# Mozard_Nano.net
KiCad netlist of a schematic drawn in EAGLE
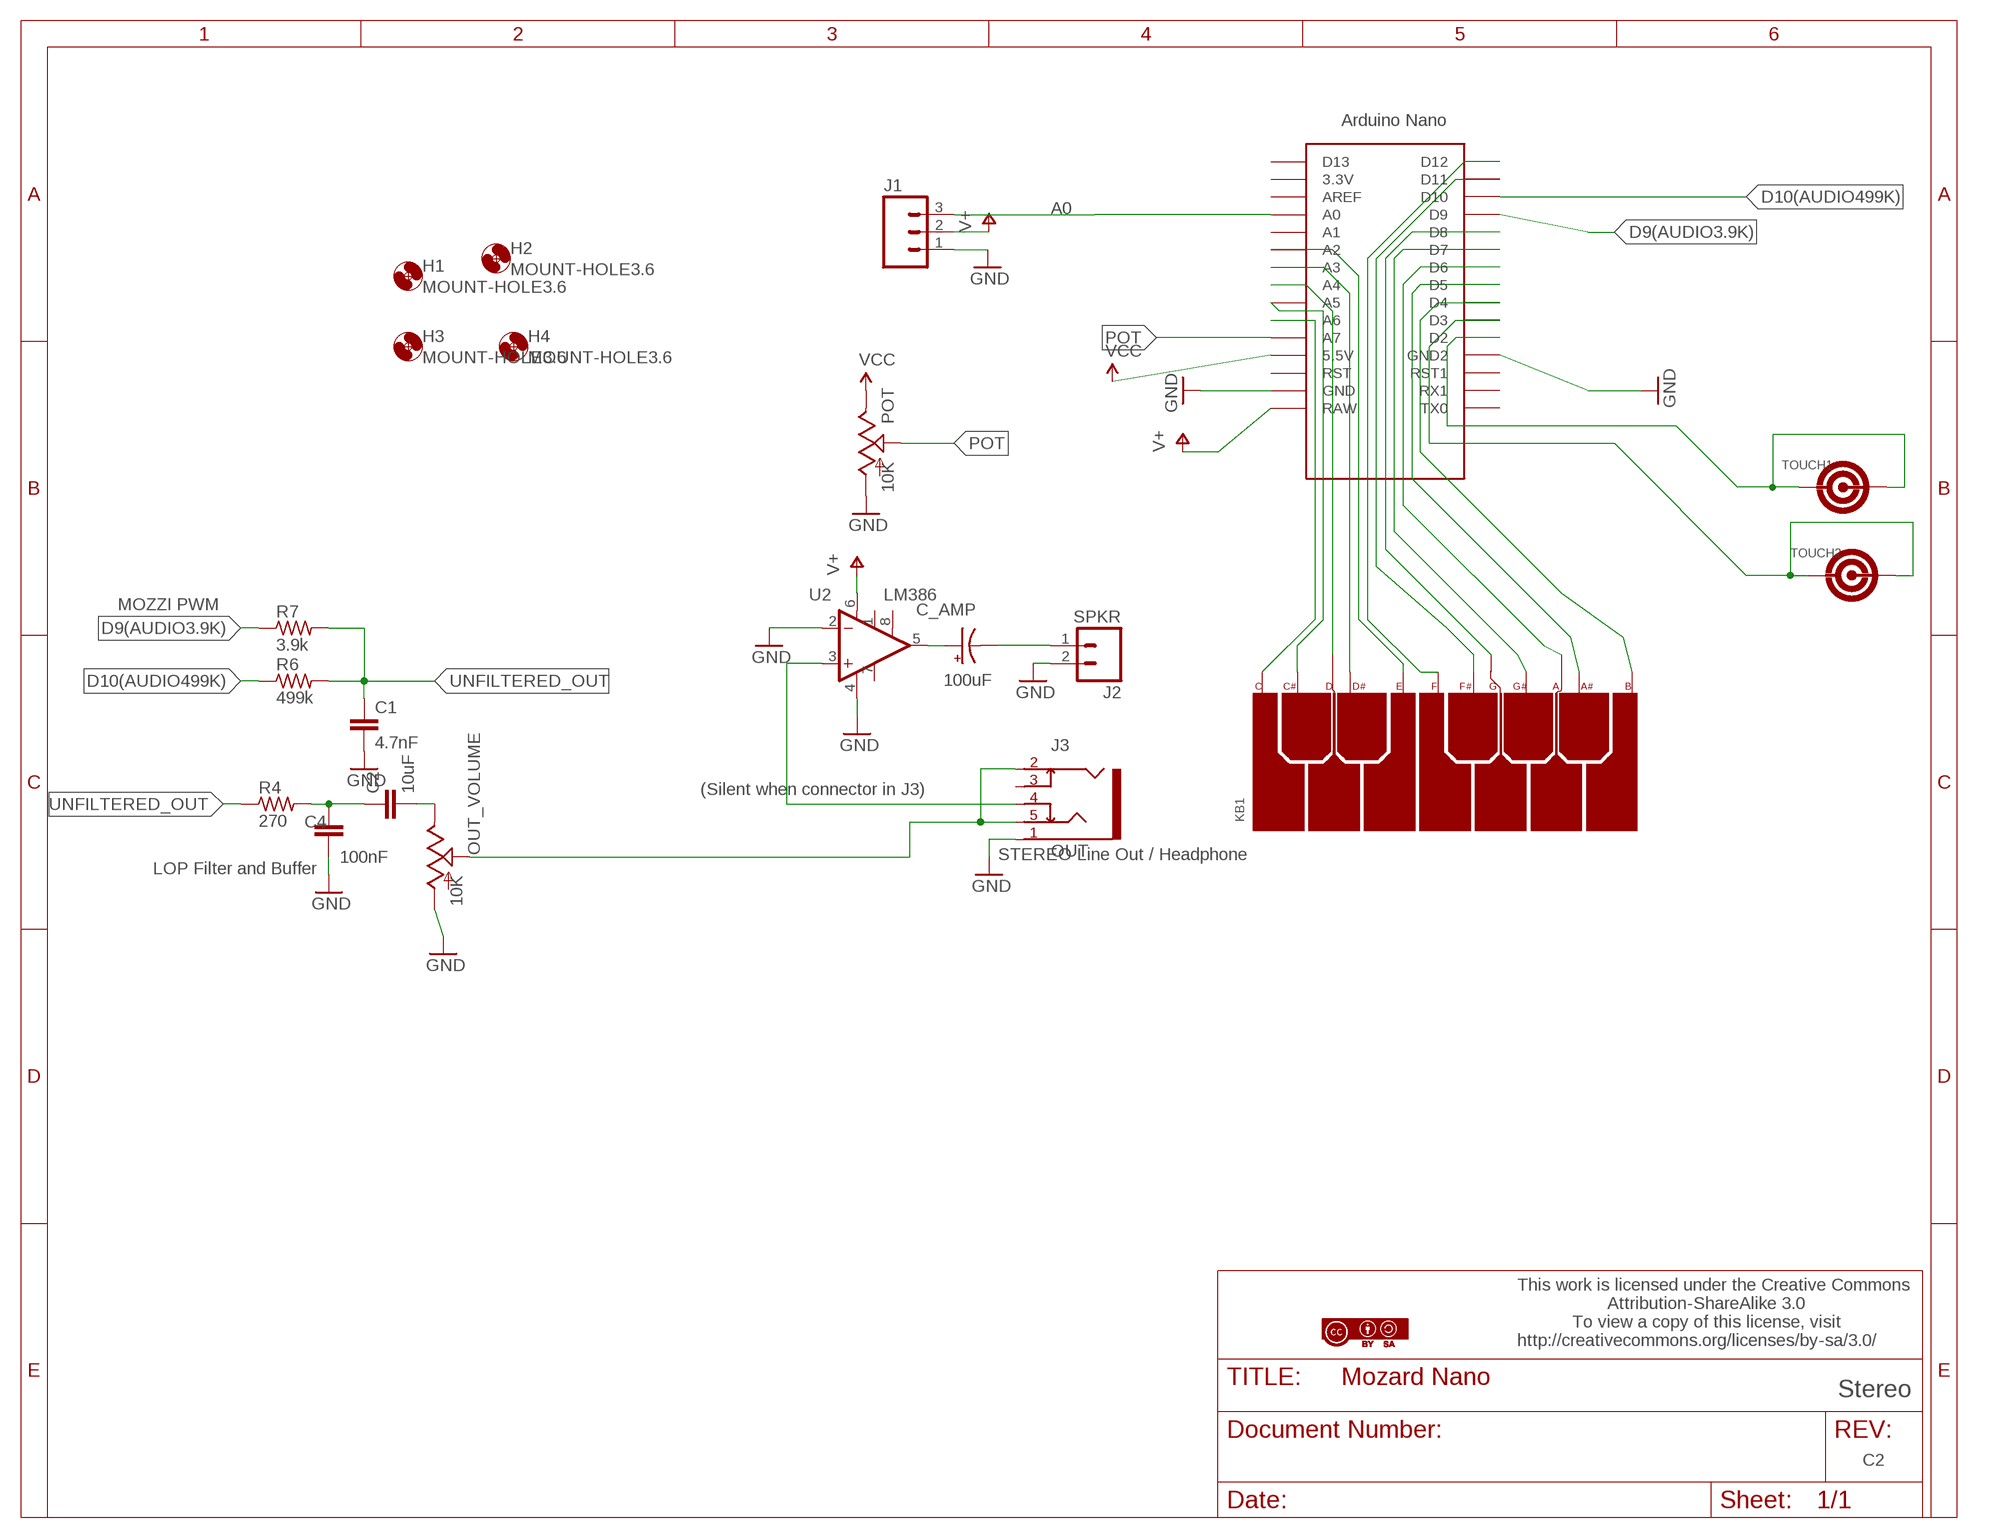
[diagram p0: schematic, sheet 1]

(export (version "E")
  (design (tool "Eeschema 10.0.6"))
  (components
    (comp (ref "C1")
      (value "4.7nF")
      (footprint "eagle-import:CAP-PTH-SMALL-KIT")
      (libsource (lib "eagle-import") (part "0.1UF-50V-20%(PTH)KIT-EZ"))
    )
    (comp (ref "C2")
      (value "10uF")
      (footprint "eagle-import:CAP-PTH-SMALL-KIT")
      (libsource (lib "eagle-import") (part "0.1UF-50V-20%(PTH)KIT-EZ"))
    )
    (comp (ref "C4")
      (value "100nF")
      (footprint "eagle-import:CAP-PTH-SMALL-KIT")
      (libsource (lib "eagle-import") (part "0.1UF-50V-20%(PTH)KIT-EZ"))
    )
    (comp (ref "C_AMP")
      (value "100uF")
      (footprint "eagle-import:CPOL-RADIAL-10UF-25V")
      (libsource (lib "eagle-import") (part "CPOL-RADIAL-10UF-25V"))
    )
    (comp (ref "H1")
      (value "MOUNT-HOLE3.6")
      (footprint "eagle-import:3,6")
      (libsource (lib "eagle-import") (part "MOUNT-HOLE3.6"))
    )
    (comp (ref "H2")
      (value "MOUNT-HOLE3.6")
      (footprint "eagle-import:3,6")
      (libsource (lib "eagle-import") (part "MOUNT-HOLE3.6"))
    )
    (comp (ref "H3")
      (value "MOUNT-HOLE3.6")
      (footprint "eagle-import:3,6")
      (libsource (lib "eagle-import") (part "MOUNT-HOLE3.6"))
    )
    (comp (ref "H4")
      (value "MOUNT-HOLE3.6")
      (footprint "eagle-import:3,6")
      (libsource (lib "eagle-import") (part "MOUNT-HOLE3.6"))
    )
    (comp (ref "J1")
      (value "M03SCREW")
      (footprint "eagle-import:SCREWTERMINAL-3.5MM-3")
      (libsource (lib "eagle-import") (part "M03SCREW"))
    )
    (comp (ref "J2")
      (value "SPKR")
      (footprint "eagle-import:SCREWTERMINAL-3.5MM-2")
      (libsource (lib "eagle-import") (part "M023.5MM"))
    )
    (comp (ref "J3")
      (value "OUT")
      (footprint "eagle-import:STEREO-AUDIO-3.5MM-SWITCHED")
      (libsource (lib "eagle-import") (part "STEREO-AUDIO-3.5MM-SWITCHED"))
    )
    (comp (ref "KB1")
      (value "PCB-KEYBOARD4")
      (footprint "eagle-import:PCB-KEYBOARD4")
      (libsource (lib "eagle-import") (part "PCB-KEYBOARD4"))
    )
    (comp (ref "OUT_VOLUME")
      (value "10K")
      (footprint "eagle-import:ALPS_POT_KIT")
      (libsource (lib "eagle-import") (part "POTALPS-KIT"))
    )
    (comp (ref "POT")
      (value "10K")
      (footprint "eagle-import:ALPS_POT_KIT")
      (libsource (lib "eagle-import") (part "POTALPS-KIT"))
    )
    (comp (ref "R4")
      (value "270")
      (footprint "eagle-import:0204_5")
      (libsource (lib "eagle-import") (part "R-US_0204/5"))
    )
    (comp (ref "R6")
      (value "499k")
      (footprint "eagle-import:0204_5")
      (libsource (lib "eagle-import") (part "R-US_0204/5"))
    )
    (comp (ref "R7")
      (value "3.9k")
      (footprint "eagle-import:0204_5")
      (libsource (lib "eagle-import") (part "R-US_0204/5"))
    )
    (comp (ref "TOUCH1")
      (value "PCB-TOUCHPAD2")
      (footprint "eagle-import:PCB-TOUCHPAD2")
      (libsource (lib "eagle-import") (part "PCB-TOUCHPAD2"))
    )
    (comp (ref "TOUCH2")
      (value "PCB-TOUCHPAD2")
      (footprint "eagle-import:PCB-TOUCHPAD2")
      (libsource (lib "eagle-import") (part "PCB-TOUCHPAD2"))
    )
    (comp (ref "U$1")
      (value "NANO")
      (footprint "eagle-import:NANO")
      (libsource (lib "eagle-import") (part "NANO"))
    )
    (comp (ref "U$2")
      (value "CC-BY-SA-LOGO2")
      (footprint "eagle-import:CC-BY-SA-LOGO2")
      (libsource (lib "eagle-import") (part "CC-BY-SA-LOGO2"))
    )
    (comp (ref "U2")
      (value "LM386")
      (footprint "eagle-import:DIP08")
      (libsource (lib "eagle-import") (part "LM386"))
    )
  )
  (nets
    (net (code "1") (name "/A0") (class "Default")
      (node (ref "J1") (pin "3") (pinfunction "3_3") (pintype "passive"))
      (node (ref "U$1") (pin "A0") (pinfunction "A0_A0") (pintype "bidirectional"))
    )
    (net (code "2") (name "D9(AUDIO3.9K)") (class "Default")
      (node (ref "R7") (pin "1") (pinfunction "1_1") (pintype "passive"))
      (node (ref "U$1") (pin "D9") (pinfunction "D9_D9") (pintype "bidirectional"))
    )
    (net (code "3") (name "D10(AUDIO499K)") (class "Default")
      (node (ref "R6") (pin "1") (pinfunction "1_1") (pintype "passive"))
      (node (ref "U$1") (pin "D10") (pinfunction "D10_D10") (pintype "bidirectional"))
    )
    (net (code "4") (name "GND") (class "Default")
      (node (ref "C1") (pin "2") (pinfunction "2_2") (pintype "passive"))
      (node (ref "C4") (pin "2") (pinfunction "2_2") (pintype "passive"))
      (node (ref "J1") (pin "1") (pinfunction "1_1") (pintype "passive"))
      (node (ref "J2") (pin "2") (pinfunction "2_2") (pintype "passive"))
      (node (ref "J3") (pin "1") (pinfunction "1_1") (pintype "bidirectional"))
      (node (ref "OUT_VOLUME") (pin "P$3") (pinfunction "A_P$3") (pintype "passive"))
      (node (ref "POT") (pin "P$3") (pinfunction "A_P$3") (pintype "passive"))
      (node (ref "U$1") (pin "GND") (pinfunction "GND_GND") (pintype "bidirectional"))
      (node (ref "U$1") (pin "GND1") (pinfunction "GND2_GND1") (pintype "bidirectional"))
      (node (ref "U2") (pin "2") (pinfunction "-IN_2") (pintype "input"))
      (node (ref "U2") (pin "4") (pinfunction "V-_4") (pintype "power_in"))
    )
    (net (code "5") (name "Net-(C2-Pad1)") (class "Default")
      (node (ref "C2") (pin "1") (pinfunction "1_1") (pintype "passive"))
      (node (ref "C4") (pin "1") (pinfunction "1_1") (pintype "passive"))
      (node (ref "R4") (pin "2") (pinfunction "2_2") (pintype "passive"))
    )
    (net (code "6") (name "Net-(C_AMP-Pad-)") (class "Default")
      (node (ref "C_AMP") (pin "-") (pinfunction "-_-") (pintype "passive"))
      (node (ref "J2") (pin "1") (pinfunction "1_1") (pintype "passive"))
    )
    (net (code "7") (name "Net-(KB1-PadA#)") (class "Default")
      (node (ref "KB1") (pin "A#") (pinfunction "A#_A#") (pintype "bidirectional"))
      (node (ref "U$1") (pin "D5") (pinfunction "D5_D5") (pintype "bidirectional"))
    )
    (net (code "8") (name "Net-(KB1-PadA)") (class "Default")
      (node (ref "KB1") (pin "A") (pinfunction "A_A") (pintype "bidirectional"))
      (node (ref "U$1") (pin "D6") (pinfunction "D6_D6") (pintype "bidirectional"))
    )
    (net (code "9") (name "Net-(KB1-PadB)") (class "Default")
      (node (ref "KB1") (pin "B") (pinfunction "B_B") (pintype "bidirectional"))
      (node (ref "U$1") (pin "D4") (pinfunction "D4_D4") (pintype "bidirectional"))
    )
    (net (code "10") (name "Net-(KB1-PadC#)") (class "Default")
      (node (ref "KB1") (pin "C#") (pinfunction "C#_C#") (pintype "bidirectional"))
      (node (ref "U$1") (pin "A5") (pinfunction "A5_A5") (pintype "bidirectional"))
    )
    (net (code "11") (name "Net-(KB1-PadC)") (class "Default")
      (node (ref "KB1") (pin "C") (pinfunction "C_C") (pintype "bidirectional"))
      (node (ref "U$1") (pin "A6") (pinfunction "A6_A6") (pintype "bidirectional"))
    )
    (net (code "12") (name "Net-(KB1-PadD#)") (class "Default")
      (node (ref "KB1") (pin "D#") (pinfunction "D#_D#") (pintype "bidirectional"))
      (node (ref "U$1") (pin "A3") (pinfunction "A3_A3") (pintype "bidirectional"))
    )
    (net (code "13") (name "Net-(KB1-PadD)") (class "Default")
      (node (ref "KB1") (pin "D") (pinfunction "D_D") (pintype "bidirectional"))
      (node (ref "U$1") (pin "A4") (pinfunction "A4_A4") (pintype "bidirectional"))
    )
    (net (code "14") (name "Net-(KB1-PadE)") (class "Default")
      (node (ref "KB1") (pin "E") (pinfunction "E_E") (pintype "bidirectional"))
      (node (ref "U$1") (pin "A2") (pinfunction "A2_A2") (pintype "bidirectional"))
    )
    (net (code "15") (name "Net-(KB1-PadF#)") (class "Default")
      (node (ref "KB1") (pin "F#") (pinfunction "F#_F#") (pintype "bidirectional"))
      (node (ref "U$1") (pin "D11") (pinfunction "D11_D11") (pintype "bidirectional"))
    )
    (net (code "16") (name "Net-(KB1-PadF)") (class "Default")
      (node (ref "KB1") (pin "F") (pinfunction "F_F") (pintype "bidirectional"))
      (node (ref "U$1") (pin "D12") (pinfunction "D12_D12") (pintype "bidirectional"))
    )
    (net (code "17") (name "Net-(KB1-PadG#)") (class "Default")
      (node (ref "KB1") (pin "G#") (pinfunction "G#_G#") (pintype "bidirectional"))
      (node (ref "U$1") (pin "D7") (pinfunction "D7_D7") (pintype "bidirectional"))
    )
    (net (code "18") (name "Net-(KB1-PadG)") (class "Default")
      (node (ref "KB1") (pin "G") (pinfunction "G_G") (pintype "bidirectional"))
      (node (ref "U$1") (pin "D8") (pinfunction "D8_D8") (pintype "bidirectional"))
    )
    (net (code "19") (name "Net-(OUT_VOLUME-E)") (class "Default")
      (node (ref "C2") (pin "2") (pinfunction "2_2") (pintype "passive"))
      (node (ref "OUT_VOLUME") (pin "P$1") (pinfunction "E_P$1") (pintype "passive"))
    )
    (net (code "20") (name "Net-(OUT_VOLUME-S)") (class "Default")
      (node (ref "J3") (pin "2") (pinfunction "2_2") (pintype "bidirectional"))
      (node (ref "J3") (pin "5") (pinfunction "5_5") (pintype "bidirectional"))
      (node (ref "OUT_VOLUME") (pin "P$2") (pinfunction "S_P$2") (pintype "passive"))
    )
    (net (code "21") (name "Net-(TOUCH1-Pad1)") (class "Default")
      (node (ref "TOUCH1") (pin "1") (pinfunction "1_1") (pintype "bidirectional"))
      (node (ref "TOUCH1") (pin "2") (pinfunction "2_2") (pintype "bidirectional"))
      (node (ref "U$1") (pin "D2") (pinfunction "D2_D2") (pintype "bidirectional"))
    )
    (net (code "22") (name "Net-(TOUCH2-Pad1)") (class "Default")
      (node (ref "TOUCH2") (pin "1") (pinfunction "1_1") (pintype "bidirectional"))
      (node (ref "TOUCH2") (pin "2") (pinfunction "2_2") (pintype "bidirectional"))
      (node (ref "U$1") (pin "D3") (pinfunction "D3_D3") (pintype "bidirectional"))
    )
    (net (code "23") (name "Net-(U2-+IN)") (class "Default")
      (node (ref "J3") (pin "4") (pinfunction "4_4") (pintype "bidirectional"))
      (node (ref "U2") (pin "3") (pinfunction "+IN_3") (pintype "input"))
    )
    (net (code "24") (name "Net-(U2-OUT)") (class "Default")
      (node (ref "C_AMP") (pin "+") (pinfunction "+_+") (pintype "passive"))
      (node (ref "U2") (pin "5") (pinfunction "OUT_5") (pintype "output"))
    )
    (net (code "25") (name "POT") (class "Default")
      (node (ref "POT") (pin "P$2") (pinfunction "S_P$2") (pintype "passive"))
      (node (ref "U$1") (pin "A7") (pinfunction "A7_A7") (pintype "bidirectional"))
    )
    (net (code "26") (name "UNFILTERED_OUT") (class "Default")
      (node (ref "C1") (pin "1") (pinfunction "1_1") (pintype "passive"))
      (node (ref "R4") (pin "1") (pinfunction "1_1") (pintype "passive"))
      (node (ref "R6") (pin "2") (pinfunction "2_2") (pintype "passive"))
      (node (ref "R7") (pin "2") (pinfunction "2_2") (pintype "passive"))
    )
    (net (code "27") (name "V+") (class "Default")
      (node (ref "J1") (pin "2") (pinfunction "2_2") (pintype "passive"))
      (node (ref "U$1") (pin "RAW") (pinfunction "RAW_RAW") (pintype "bidirectional"))
      (node (ref "U2") (pin "6") (pinfunction "V+_6") (pintype "power_in"))
    )
    (net (code "28") (name "VCC") (class "Default")
      (node (ref "POT") (pin "P$1") (pinfunction "E_P$1") (pintype "passive"))
      (node (ref "U$1") (pin "5V") (pinfunction "5.5V_5V") (pintype "bidirectional"))
    )
    (net (code "29") (name "unconnected-(J3-Pad3)") (class "Default")
      (node (ref "J3") (pin "3") (pinfunction "3_3") (pintype "bidirectional"))
    )
    (net (code "30") (name "unconnected-(U$1-Pad3.3V)") (class "Default")
      (node (ref "U$1") (pin "3.3V") (pinfunction "3.3V_3.3V") (pintype "bidirectional"))
    )
    (net (code "31") (name "unconnected-(U$1-PadA1)") (class "Default")
      (node (ref "U$1") (pin "A1") (pinfunction "A1_A1") (pintype "bidirectional"))
    )
    (net (code "32") (name "unconnected-(U$1-PadAREF)") (class "Default")
      (node (ref "U$1") (pin "AREF") (pinfunction "AREF_AREF") (pintype "bidirectional"))
    )
    (net (code "33") (name "unconnected-(U$1-PadD13)") (class "Default")
      (node (ref "U$1") (pin "D13") (pinfunction "D13_D13") (pintype "bidirectional"))
    )
    (net (code "34") (name "unconnected-(U$1-PadRST)") (class "Default")
      (node (ref "U$1") (pin "RST") (pinfunction "RST_RST") (pintype "bidirectional"))
    )
    (net (code "35") (name "unconnected-(U$1-PadRST1)") (class "Default")
      (node (ref "U$1") (pin "RST1") (pinfunction "RST1_RST1") (pintype "bidirectional"))
    )
    (net (code "36") (name "unconnected-(U$1-PadRX1)") (class "Default")
      (node (ref "U$1") (pin "RX1") (pinfunction "RX1_RX1") (pintype "bidirectional"))
    )
    (net (code "37") (name "unconnected-(U$1-PadTX0)") (class "Default")
      (node (ref "U$1") (pin "TX0") (pinfunction "TX0_TX0") (pintype "bidirectional"))
    )
    (net (code "38") (name "unconnected-(U2-BP-Pad7)") (class "Default")
      (node (ref "U2") (pin "7") (pinfunction "BP_7") (pintype "bidirectional"))
    )
    (net (code "39") (name "unconnected-(U2-GAIN-Pad1)") (class "Default")
      (node (ref "U2") (pin "1") (pinfunction "GAIN_1") (pintype "bidirectional"))
    )
    (net (code "40") (name "unconnected-(U2-GAIN-Pad8)") (class "Default")
      (node (ref "U2") (pin "8") (pinfunction "GAIN_8") (pintype "bidirectional"))
    )
  )
)
